# Interface.net
KiCad netlist of a schematic drawn in Altium Designer
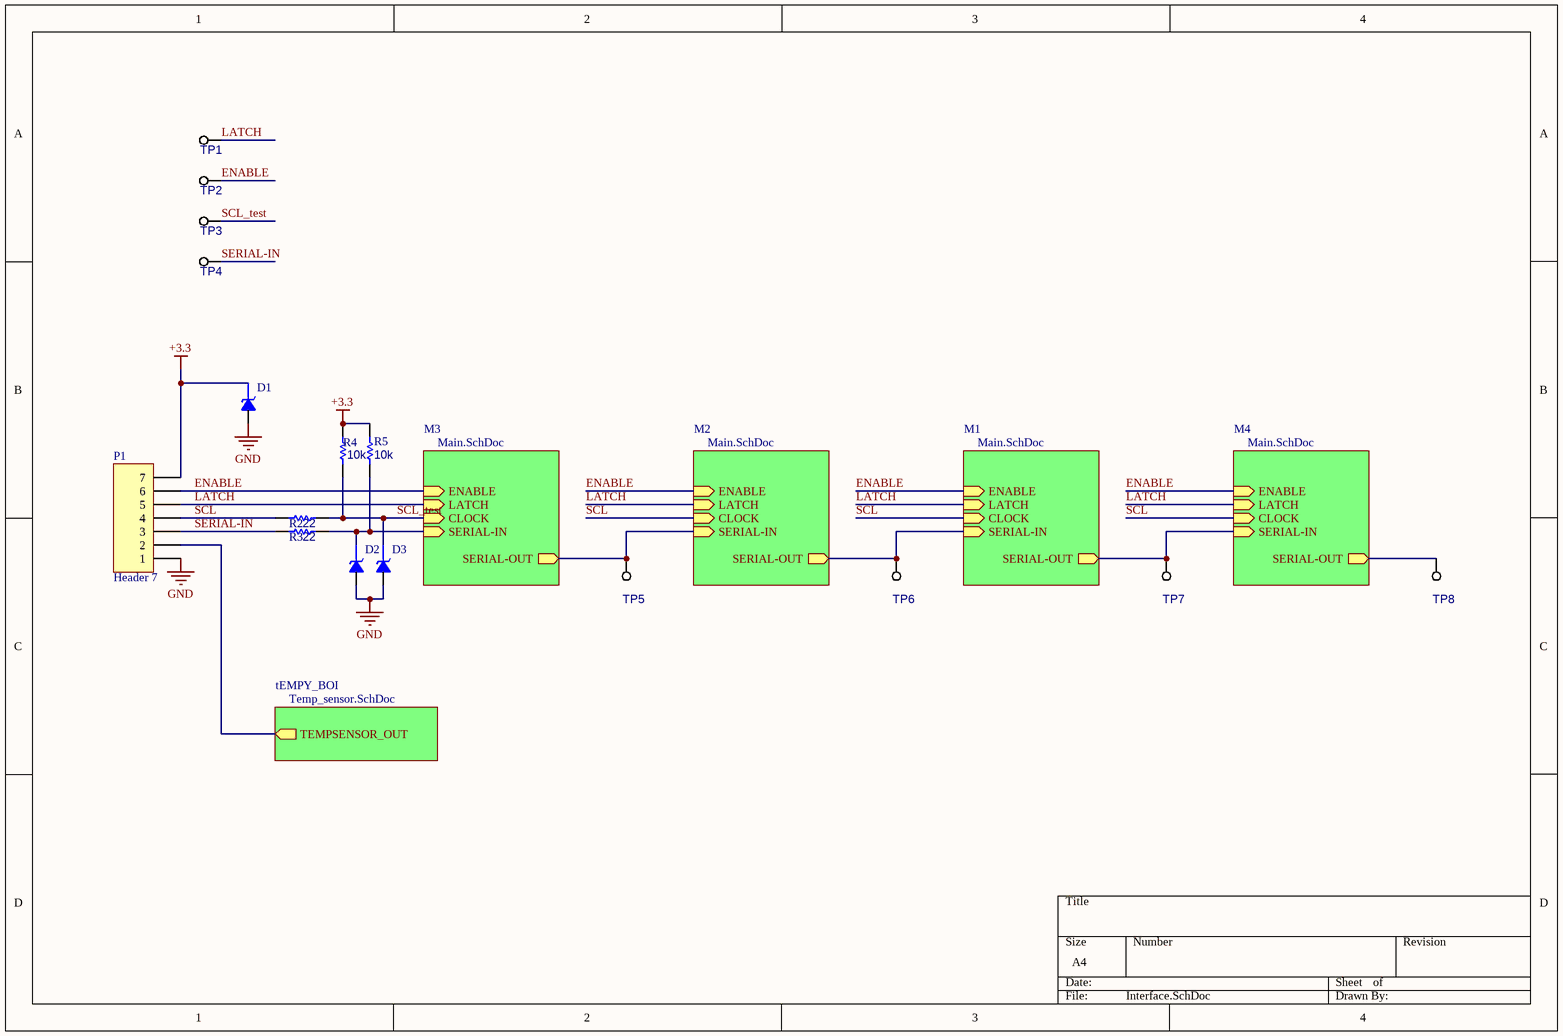
[diagram p0: Interface.SchDoc]

(export (version "E")
  (design (tool "Eeschema 10.0.6"))
  (components
    (comp (ref "D1")
      (value "STS521033B950")
      (footprint "STS521033B950_COB")
      (description "3.3V ESD Diode")
      (fields (field (name "COPYRIGHT") "Copyright (C) 2023 Ultra Librarian. All rights reserved."))
      (libsource (lib "Space Concordia") (part "STS521033B950"))
    )
    (comp (ref "D2")
      (value "STS521033B950")
      (footprint "STS521033B950_COB")
      (description "3.3V ESD Diode")
      (fields (field (name "COPYRIGHT") "Copyright (C) 2023 Ultra Librarian. All rights reserved."))
      (libsource (lib "Space Concordia") (part "STS521033B950"))
    )
    (comp (ref "D3")
      (value "STS521033B950")
      (footprint "STS521033B950_COB")
      (description "3.3V ESD Diode")
      (fields (field (name "COPYRIGHT") "Copyright (C) 2023 Ultra Librarian. All rights reserved."))
      (libsource (lib "Space Concordia") (part "STS521033B950"))
    )
    (comp (ref "P1")
      (value "Header 7")
      (footprint "HDR1X7")
      (description "Header, 7-Pin")
      (fields (field (name "PUBLISHER") "Altium Limited"))
      (libsource (lib "Space Concordia") (part "Header 7H"))
    )
    (comp (ref "R2")
      (value "22")
      (footprint "R0603A")
      (description "Resistor")
      (libsource (lib "Space Concordia") (part "Resistor"))
    )
    (comp (ref "R3")
      (value "22")
      (footprint "R0603A")
      (description "Resistor")
      (libsource (lib "Space Concordia") (part "Resistor"))
    )
    (comp (ref "R4")
      (value "10k")
      (footprint "R0603A")
      (description "Resistor")
      (libsource (lib "Space Concordia") (part "Resistor"))
    )
    (comp (ref "R5")
      (value "10k")
      (footprint "R0603A")
      (description "Resistor")
      (libsource (lib "Space Concordia") (part "Resistor"))
    )
    (comp (ref "TP1")
      (value "Test Point")
      (footprint "TP-SMT-1mm")
      (description "In circuit test point for a net")
      (libsource (lib "Space Concordia") (part "Test Point"))
    )
    (comp (ref "TP2")
      (value "Test Point")
      (footprint "TP-SMT-1mm")
      (description "In circuit test point for a net")
      (libsource (lib "Space Concordia") (part "Test Point"))
    )
    (comp (ref "TP3")
      (value "Test Point")
      (footprint "TP-SMT-1mm")
      (description "In circuit test point for a net")
      (libsource (lib "Space Concordia") (part "Test Point"))
    )
    (comp (ref "TP4")
      (value "Test Point")
      (footprint "TP-SMT-1mm")
      (description "In circuit test point for a net")
      (libsource (lib "Space Concordia") (part "Test Point"))
    )
    (comp (ref "TP5")
      (value "Test Point")
      (footprint "TP-SMT-1mm")
      (description "In circuit test point for a net")
      (libsource (lib "Space Concordia") (part "Test Point"))
    )
    (comp (ref "TP6")
      (value "Test Point")
      (footprint "TP-SMT-1mm")
      (description "In circuit test point for a net")
      (libsource (lib "Space Concordia") (part "Test Point"))
    )
    (comp (ref "TP7")
      (value "Test Point")
      (footprint "TP-SMT-1mm")
      (description "In circuit test point for a net")
      (libsource (lib "Space Concordia") (part "Test Point"))
    )
    (comp (ref "TP8")
      (value "Test Point")
      (footprint "TP-SMT-1mm")
      (description "In circuit test point for a net")
      (libsource (lib "Space Concordia") (part "Test Point"))
    )
  )
  (nets
    (net (code "1") (name "+3.3") (class "Default")
      (node (ref "D1") (pin "1") (pinfunction "K_1") (pintype "passive"))
      (node (ref "P1") (pin "7") (pinfunction "7_7") (pintype "passive"))
      (node (ref "R4") (pin "1") (pinfunction "1_1") (pintype "passive"))
      (node (ref "R5") (pin "1") (pinfunction "1_1") (pintype "passive"))
    )
    (net (code "2") (name "/ENABLE") (class "Default")
      (node (ref "P1") (pin "6") (pinfunction "6_6") (pintype "passive"))
      (node (ref "TP2") (pin "1") (pinfunction "Pad_1") (pintype "passive"))
    )
    (net (code "3") (name "/LATCH") (class "Default")
      (node (ref "P1") (pin "5") (pinfunction "5_5") (pintype "passive"))
      (node (ref "TP1") (pin "1") (pinfunction "Pad_1") (pintype "passive"))
    )
    (net (code "4") (name "/SCL") (class "Default")
      (node (ref "P1") (pin "4") (pinfunction "4_4") (pintype "passive"))
      (node (ref "R2") (pin "2") (pinfunction "2_2") (pintype "passive"))
    )
    (net (code "5") (name "/SCL_test") (class "Default")
      (node (ref "D3") (pin "1") (pinfunction "K_1") (pintype "passive"))
      (node (ref "R2") (pin "1") (pinfunction "1_1") (pintype "passive"))
      (node (ref "R4") (pin "2") (pinfunction "2_2") (pintype "passive"))
      (node (ref "TP3") (pin "1") (pinfunction "Pad_1") (pintype "passive"))
    )
    (net (code "6") (name "/SERIAL-IN") (class "Default")
      (node (ref "P1") (pin "3") (pinfunction "3_3") (pintype "passive"))
      (node (ref "R3") (pin "2") (pinfunction "2_2") (pintype "passive"))
      (node (ref "TP4") (pin "1") (pinfunction "Pad_1") (pintype "passive"))
    )
    (net (code "7") (name "/SERIAL-IN_1") (class "Default")
      (node (ref "D2") (pin "1") (pinfunction "K_1") (pintype "passive"))
      (node (ref "R3") (pin "1") (pinfunction "1_1") (pintype "passive"))
      (node (ref "R5") (pin "2") (pinfunction "2_2") (pintype "passive"))
    )
    (net (code "8") (name "/SERIAL-OUT") (class "Default")
      (node (ref "TP8") (pin "1") (pinfunction "Pad_1") (pintype "passive"))
    )
    (net (code "9") (name "/SERIAL-OUT_1") (class "Default")
      (node (ref "TP5") (pin "1") (pinfunction "Pad_1") (pintype "passive"))
    )
    (net (code "10") (name "/SERIAL-OUT_2") (class "Default")
      (node (ref "TP6") (pin "1") (pinfunction "Pad_1") (pintype "passive"))
    )
    (net (code "11") (name "/SERIAL-OUT_3") (class "Default")
      (node (ref "TP7") (pin "1") (pinfunction "Pad_1") (pintype "passive"))
    )
    (net (code "12") (name "/TEMPSENSOR_OUT") (class "Default")
      (node (ref "P1") (pin "2") (pinfunction "2_2") (pintype "passive"))
    )
    (net (code "13") (name "GND") (class "Default")
      (node (ref "D1") (pin "2") (pinfunction "A_2") (pintype "passive"))
      (node (ref "D2") (pin "2") (pinfunction "A_2") (pintype "passive"))
      (node (ref "D3") (pin "2") (pinfunction "A_2") (pintype "passive"))
      (node (ref "P1") (pin "1") (pinfunction "1_1") (pintype "passive"))
    )
  )
)
